# FPGA_Power.net
KiCad netlist of a schematic drawn in Altium Designer
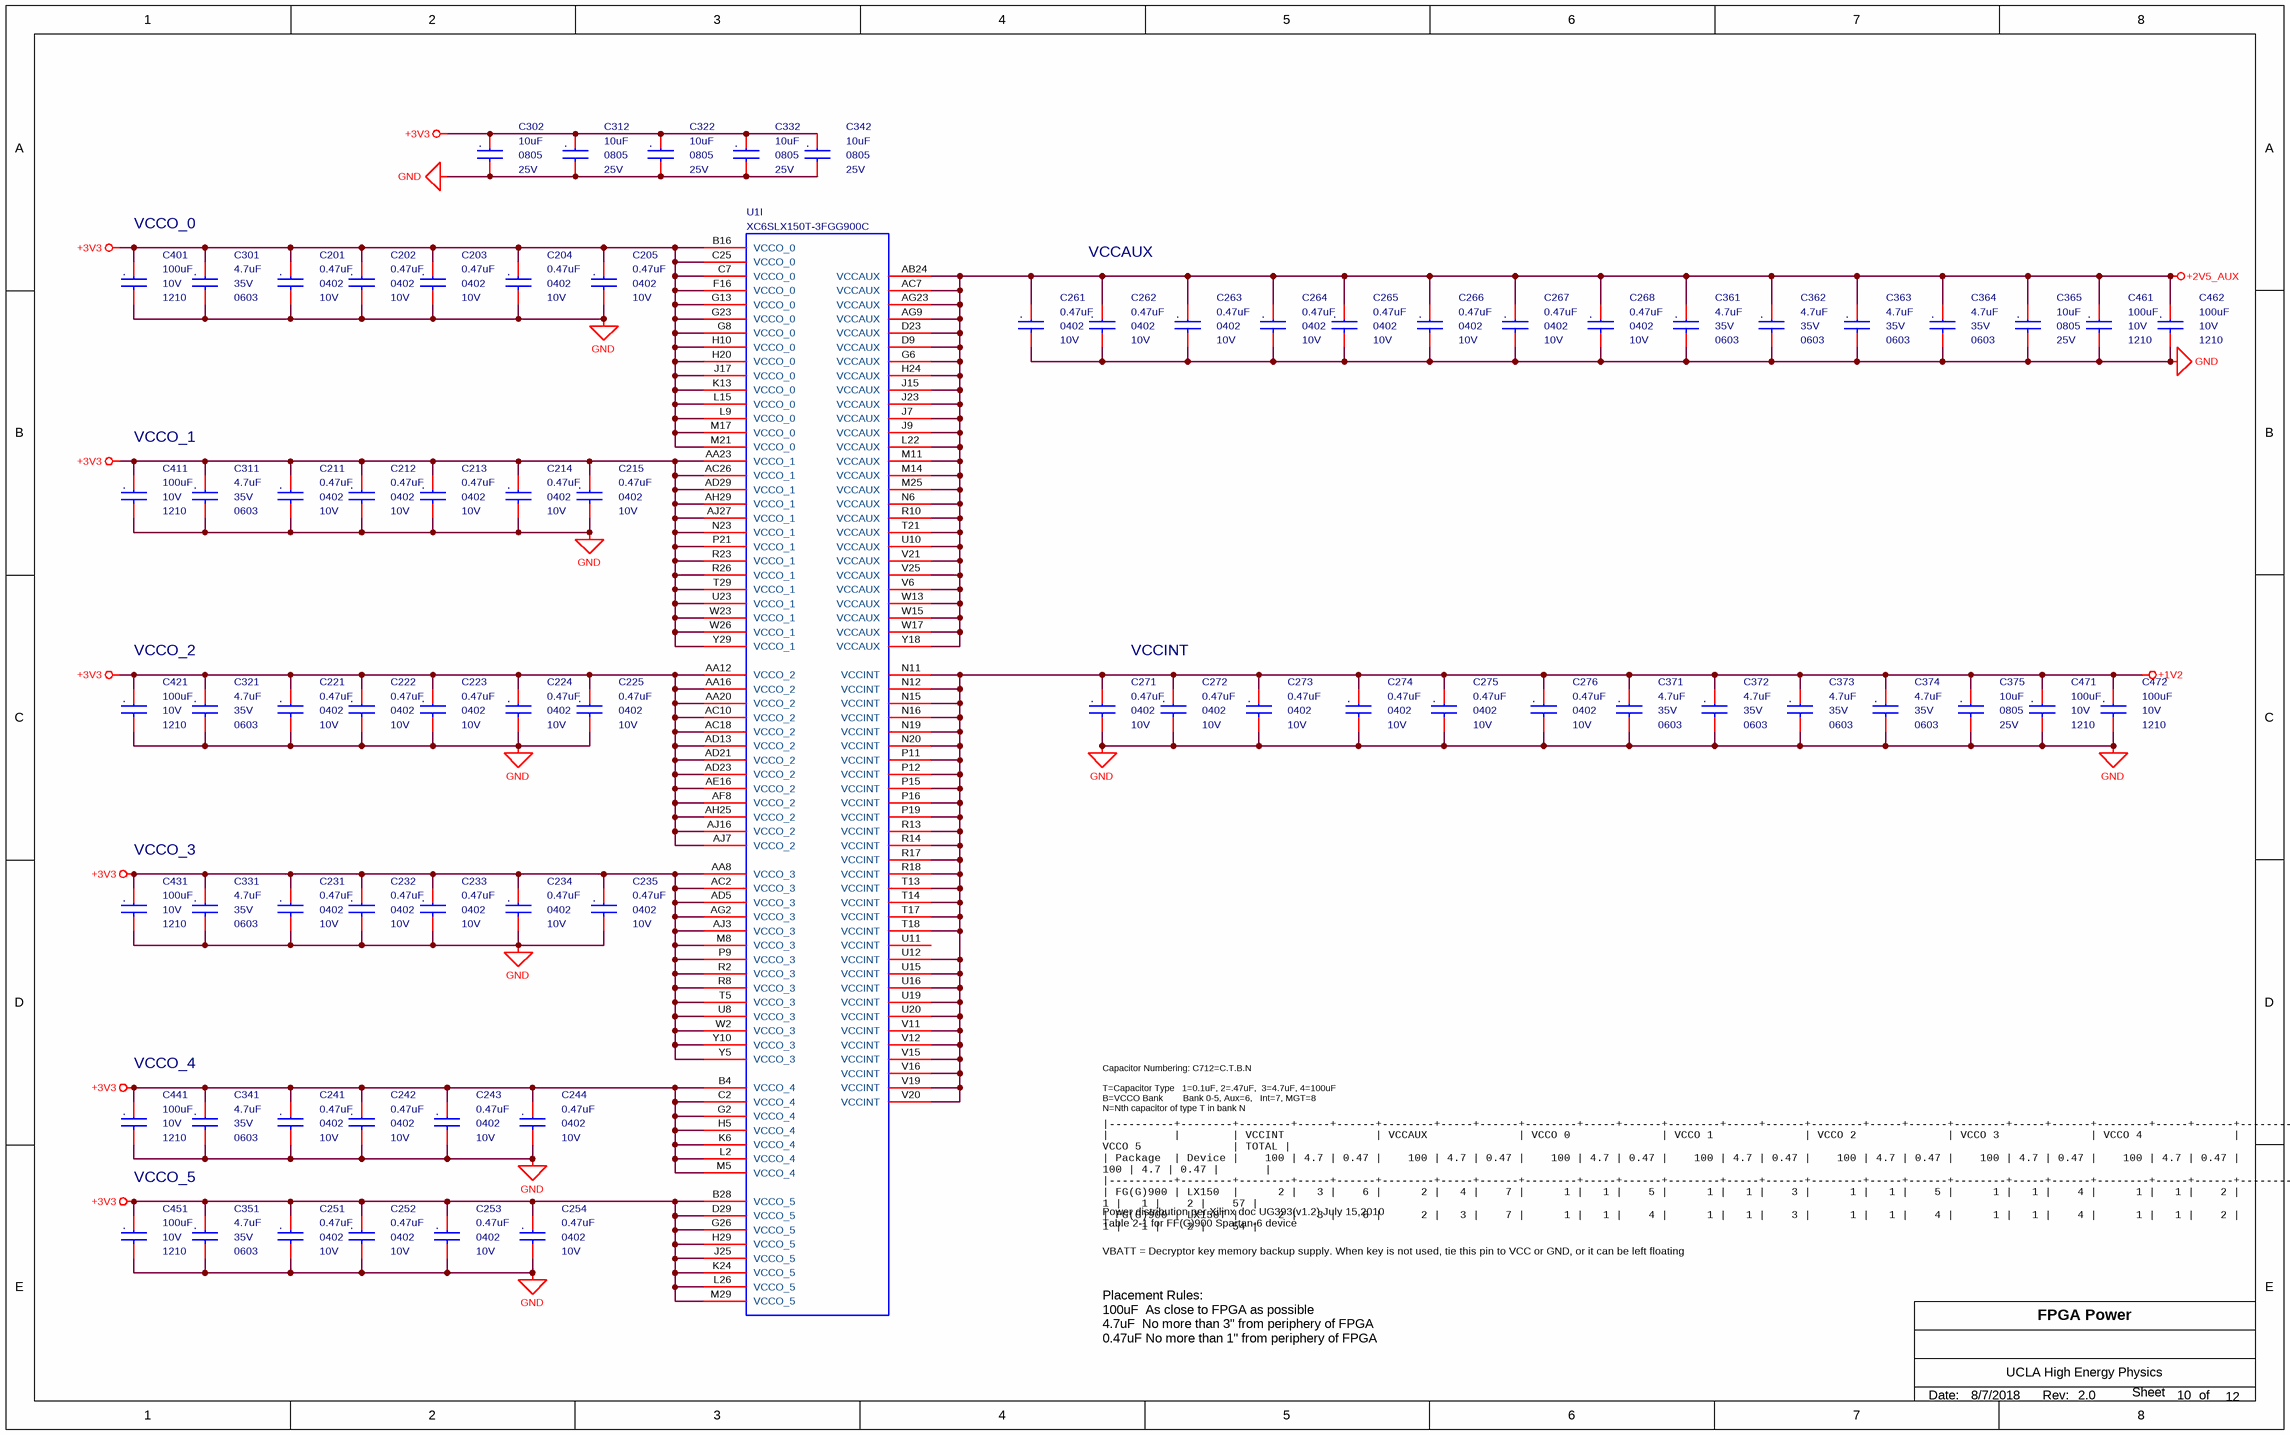
[diagram p0: FPGA_Power.SchDoc]

(export (version "E")
  (design (tool "Eeschema 10.0.6"))
  (components
    (comp (ref "C201")
      (value "0.47uF")
      (footprint "MC_S6/SM/C_0402_IPC")
      (description "CAP CER 0.47UF 10V X5R 0402")
      (fields
        (field (name "MANUFACTURER") "Murata Electronics North America")
        (field (name "MANUFACTURER PART NUMBER") "GRM155R61A474KE15J")
        (field (name "VOLTAGE - RATED") "10V")
        (field (name "PACKAGE") "0402")
      )
      (libsource (lib "ALCT_MEZ_SPARTAN6_Library") (part "GRM155R61A474KE15J"))
    )
    (comp (ref "C202")
      (value "0.47uF")
      (footprint "MC_S6/SM/C_0402_IPC")
      (description "CAP CER 0.47UF 10V X5R 0402")
      (fields
        (field (name "MANUFACTURER") "Murata Electronics North America")
        (field (name "MANUFACTURER PART NUMBER") "GRM155R61A474KE15J")
        (field (name "VOLTAGE - RATED") "10V")
        (field (name "PACKAGE") "0402")
      )
      (libsource (lib "ALCT_MEZ_SPARTAN6_Library") (part "GRM155R61A474KE15J"))
    )
    (comp (ref "C203")
      (value "0.47uF")
      (footprint "MC_S6/SM/C_0402_IPC")
      (description "CAP CER 0.47UF 10V X5R 0402")
      (fields
        (field (name "MANUFACTURER") "Murata Electronics North America")
        (field (name "MANUFACTURER PART NUMBER") "GRM155R61A474KE15J")
        (field (name "VOLTAGE - RATED") "10V")
        (field (name "PACKAGE") "0402")
      )
      (libsource (lib "ALCT_MEZ_SPARTAN6_Library") (part "GRM155R61A474KE15J"))
    )
    (comp (ref "C204")
      (value "0.47uF")
      (footprint "MC_S6/SM/C_0402_IPC")
      (description "CAP CER 0.47UF 10V X5R 0402")
      (fields
        (field (name "MANUFACTURER") "Murata Electronics North America")
        (field (name "MANUFACTURER PART NUMBER") "GRM155R61A474KE15J")
        (field (name "VOLTAGE - RATED") "10V")
        (field (name "PACKAGE") "0402")
      )
      (libsource (lib "ALCT_MEZ_SPARTAN6_Library") (part "GRM155R61A474KE15J"))
    )
    (comp (ref "C205")
      (value "0.47uF")
      (footprint "MC_S6/SM/C_0402_IPC")
      (description "CAP CER 0.47UF 10V X5R 0402")
      (fields
        (field (name "MANUFACTURER") "Murata Electronics North America")
        (field (name "MANUFACTURER PART NUMBER") "GRM155R61A474KE15J")
        (field (name "VOLTAGE - RATED") "10V")
        (field (name "PACKAGE") "0402")
      )
      (libsource (lib "ALCT_MEZ_SPARTAN6_Library") (part "GRM155R61A474KE15J"))
    )
    (comp (ref "C211")
      (value "0.47uF")
      (footprint "MC_S6/SM/C_0402_IPC")
      (description "CAP CER 0.47UF 10V X5R 0402")
      (fields
        (field (name "MANUFACTURER") "Murata Electronics North America")
        (field (name "MANUFACTURER PART NUMBER") "GRM155R61A474KE15J")
        (field (name "VOLTAGE - RATED") "10V")
        (field (name "PACKAGE") "0402")
      )
      (libsource (lib "ALCT_MEZ_SPARTAN6_Library") (part "GRM155R61A474KE15J"))
    )
    (comp (ref "C212")
      (value "0.47uF")
      (footprint "MC_S6/SM/C_0402_IPC")
      (description "CAP CER 0.47UF 10V X5R 0402")
      (fields
        (field (name "MANUFACTURER") "Murata Electronics North America")
        (field (name "MANUFACTURER PART NUMBER") "GRM155R61A474KE15J")
        (field (name "VOLTAGE - RATED") "10V")
        (field (name "PACKAGE") "0402")
      )
      (libsource (lib "ALCT_MEZ_SPARTAN6_Library") (part "GRM155R61A474KE15J"))
    )
    (comp (ref "C213")
      (value "0.47uF")
      (footprint "MC_S6/SM/C_0402_IPC")
      (description "CAP CER 0.47UF 10V X5R 0402")
      (fields
        (field (name "MANUFACTURER") "Murata Electronics North America")
        (field (name "MANUFACTURER PART NUMBER") "GRM155R61A474KE15J")
        (field (name "VOLTAGE - RATED") "10V")
        (field (name "PACKAGE") "0402")
      )
      (libsource (lib "ALCT_MEZ_SPARTAN6_Library") (part "GRM155R61A474KE15J"))
    )
    (comp (ref "C214")
      (value "0.47uF")
      (footprint "MC_S6/SM/C_0402_IPC")
      (description "CAP CER 0.47UF 10V X5R 0402")
      (fields
        (field (name "MANUFACTURER") "Murata Electronics North America")
        (field (name "MANUFACTURER PART NUMBER") "GRM155R61A474KE15J")
        (field (name "VOLTAGE - RATED") "10V")
        (field (name "PACKAGE") "0402")
      )
      (libsource (lib "ALCT_MEZ_SPARTAN6_Library") (part "GRM155R61A474KE15J"))
    )
    (comp (ref "C215")
      (value "0.47uF")
      (footprint "MC_S6/SM/C_0402_IPC")
      (description "CAP CER 0.47UF 10V X5R 0402")
      (fields
        (field (name "MANUFACTURER") "Murata Electronics North America")
        (field (name "MANUFACTURER PART NUMBER") "GRM155R61A474KE15J")
        (field (name "VOLTAGE - RATED") "10V")
        (field (name "PACKAGE") "0402")
      )
      (libsource (lib "ALCT_MEZ_SPARTAN6_Library") (part "GRM155R61A474KE15J"))
    )
    (comp (ref "C221")
      (value "0.47uF")
      (footprint "MC_S6/SM/C_0402_IPC")
      (description "CAP CER 0.47UF 10V X5R 0402")
      (fields
        (field (name "MANUFACTURER") "Murata Electronics North America")
        (field (name "MANUFACTURER PART NUMBER") "GRM155R61A474KE15J")
        (field (name "VOLTAGE - RATED") "10V")
        (field (name "PACKAGE") "0402")
      )
      (libsource (lib "ALCT_MEZ_SPARTAN6_Library") (part "GRM155R61A474KE15J"))
    )
    (comp (ref "C222")
      (value "0.47uF")
      (footprint "MC_S6/SM/C_0402_IPC")
      (description "CAP CER 0.47UF 10V X5R 0402")
      (fields
        (field (name "MANUFACTURER") "Murata Electronics North America")
        (field (name "MANUFACTURER PART NUMBER") "GRM155R61A474KE15J")
        (field (name "VOLTAGE - RATED") "10V")
        (field (name "PACKAGE") "0402")
      )
      (libsource (lib "ALCT_MEZ_SPARTAN6_Library") (part "GRM155R61A474KE15J"))
    )
    (comp (ref "C223")
      (value "0.47uF")
      (footprint "MC_S6/SM/C_0402_IPC")
      (description "CAP CER 0.47UF 10V X5R 0402")
      (fields
        (field (name "MANUFACTURER") "Murata Electronics North America")
        (field (name "MANUFACTURER PART NUMBER") "GRM155R61A474KE15J")
        (field (name "VOLTAGE - RATED") "10V")
        (field (name "PACKAGE") "0402")
      )
      (libsource (lib "ALCT_MEZ_SPARTAN6_Library") (part "GRM155R61A474KE15J"))
    )
    (comp (ref "C224")
      (value "0.47uF")
      (footprint "MC_S6/SM/C_0402_IPC")
      (description "CAP CER 0.47UF 10V X5R 0402")
      (fields
        (field (name "MANUFACTURER") "Murata Electronics North America")
        (field (name "MANUFACTURER PART NUMBER") "GRM155R61A474KE15J")
        (field (name "VOLTAGE - RATED") "10V")
        (field (name "PACKAGE") "0402")
      )
      (libsource (lib "ALCT_MEZ_SPARTAN6_Library") (part "GRM155R61A474KE15J"))
    )
    (comp (ref "C225")
      (value "0.47uF")
      (footprint "MC_S6/SM/C_0402_IPC")
      (description "CAP CER 0.47UF 10V X5R 0402")
      (fields
        (field (name "MANUFACTURER") "Murata Electronics North America")
        (field (name "MANUFACTURER PART NUMBER") "GRM155R61A474KE15J")
        (field (name "VOLTAGE - RATED") "10V")
        (field (name "PACKAGE") "0402")
      )
      (libsource (lib "ALCT_MEZ_SPARTAN6_Library") (part "GRM155R61A474KE15J"))
    )
    (comp (ref "C231")
      (value "0.47uF")
      (footprint "MC_S6/SM/C_0402_IPC")
      (description "CAP CER 0.47UF 10V X5R 0402")
      (fields
        (field (name "MANUFACTURER") "Murata Electronics North America")
        (field (name "MANUFACTURER PART NUMBER") "GRM155R61A474KE15J")
        (field (name "VOLTAGE - RATED") "10V")
        (field (name "PACKAGE") "0402")
      )
      (libsource (lib "ALCT_MEZ_SPARTAN6_Library") (part "GRM155R61A474KE15J"))
    )
    (comp (ref "C232")
      (value "0.47uF")
      (footprint "MC_S6/SM/C_0402_IPC")
      (description "CAP CER 0.47UF 10V X5R 0402")
      (fields
        (field (name "MANUFACTURER") "Murata Electronics North America")
        (field (name "MANUFACTURER PART NUMBER") "GRM155R61A474KE15J")
        (field (name "VOLTAGE - RATED") "10V")
        (field (name "PACKAGE") "0402")
      )
      (libsource (lib "ALCT_MEZ_SPARTAN6_Library") (part "GRM155R61A474KE15J"))
    )
    (comp (ref "C233")
      (value "0.47uF")
      (footprint "MC_S6/SM/C_0402_IPC")
      (description "CAP CER 0.47UF 10V X5R 0402")
      (fields
        (field (name "MANUFACTURER") "Murata Electronics North America")
        (field (name "MANUFACTURER PART NUMBER") "GRM155R61A474KE15J")
        (field (name "VOLTAGE - RATED") "10V")
        (field (name "PACKAGE") "0402")
      )
      (libsource (lib "ALCT_MEZ_SPARTAN6_Library") (part "GRM155R61A474KE15J"))
    )
    (comp (ref "C234")
      (value "0.47uF")
      (footprint "MC_S6/SM/C_0402_IPC")
      (description "CAP CER 0.47UF 10V X5R 0402")
      (fields
        (field (name "MANUFACTURER") "Murata Electronics North America")
        (field (name "MANUFACTURER PART NUMBER") "GRM155R61A474KE15J")
        (field (name "VOLTAGE - RATED") "10V")
        (field (name "PACKAGE") "0402")
      )
      (libsource (lib "ALCT_MEZ_SPARTAN6_Library") (part "GRM155R61A474KE15J"))
    )
    (comp (ref "C235")
      (value "0.47uF")
      (footprint "MC_S6/SM/C_0402_IPC")
      (description "CAP CER 0.47UF 10V X5R 0402")
      (fields
        (field (name "MANUFACTURER") "Murata Electronics North America")
        (field (name "MANUFACTURER PART NUMBER") "GRM155R61A474KE15J")
        (field (name "VOLTAGE - RATED") "10V")
        (field (name "PACKAGE") "0402")
      )
      (libsource (lib "ALCT_MEZ_SPARTAN6_Library") (part "GRM155R61A474KE15J"))
    )
    (comp (ref "C241")
      (value "0.47uF")
      (footprint "MC_S6/SM/C_0402_IPC")
      (description "CAP CER 0.47UF 10V X5R 0402")
      (fields
        (field (name "MANUFACTURER") "Murata Electronics North America")
        (field (name "MANUFACTURER PART NUMBER") "GRM155R61A474KE15J")
        (field (name "VOLTAGE - RATED") "10V")
        (field (name "PACKAGE") "0402")
      )
      (libsource (lib "ALCT_MEZ_SPARTAN6_Library") (part "GRM155R61A474KE15J"))
    )
    (comp (ref "C242")
      (value "0.47uF")
      (footprint "MC_S6/SM/C_0402_IPC")
      (description "CAP CER 0.47UF 10V X5R 0402")
      (fields
        (field (name "MANUFACTURER") "Murata Electronics North America")
        (field (name "MANUFACTURER PART NUMBER") "GRM155R61A474KE15J")
        (field (name "VOLTAGE - RATED") "10V")
        (field (name "PACKAGE") "0402")
      )
      (libsource (lib "ALCT_MEZ_SPARTAN6_Library") (part "GRM155R61A474KE15J"))
    )
    (comp (ref "C243")
      (value "0.47uF")
      (footprint "MC_S6/SM/C_0402_IPC")
      (description "CAP CER 0.47UF 10V X5R 0402")
      (fields
        (field (name "MANUFACTURER") "Murata Electronics North America")
        (field (name "MANUFACTURER PART NUMBER") "GRM155R61A474KE15J")
        (field (name "VOLTAGE - RATED") "10V")
        (field (name "PACKAGE") "0402")
      )
      (libsource (lib "ALCT_MEZ_SPARTAN6_Library") (part "GRM155R61A474KE15J"))
    )
    (comp (ref "C244")
      (value "0.47uF")
      (footprint "MC_S6/SM/C_0402_IPC")
      (description "CAP CER 0.47UF 10V X5R 0402")
      (fields
        (field (name "MANUFACTURER") "Murata Electronics North America")
        (field (name "MANUFACTURER PART NUMBER") "GRM155R61A474KE15J")
        (field (name "VOLTAGE - RATED") "10V")
        (field (name "PACKAGE") "0402")
      )
      (libsource (lib "ALCT_MEZ_SPARTAN6_Library") (part "GRM155R61A474KE15J"))
    )
    (comp (ref "C251")
      (value "0.47uF")
      (footprint "MC_S6/SM/C_0402_IPC")
      (description "CAP CER 0.47UF 10V X5R 0402")
      (fields
        (field (name "MANUFACTURER") "Murata Electronics North America")
        (field (name "MANUFACTURER PART NUMBER") "GRM155R61A474KE15J")
        (field (name "VOLTAGE - RATED") "10V")
        (field (name "PACKAGE") "0402")
      )
      (libsource (lib "ALCT_MEZ_SPARTAN6_Library") (part "GRM155R61A474KE15J"))
    )
    (comp (ref "C252")
      (value "0.47uF")
      (footprint "MC_S6/SM/C_0402_IPC")
      (description "CAP CER 0.47UF 10V X5R 0402")
      (fields
        (field (name "MANUFACTURER") "Murata Electronics North America")
        (field (name "MANUFACTURER PART NUMBER") "GRM155R61A474KE15J")
        (field (name "VOLTAGE - RATED") "10V")
        (field (name "PACKAGE") "0402")
      )
      (libsource (lib "ALCT_MEZ_SPARTAN6_Library") (part "GRM155R61A474KE15J"))
    )
    (comp (ref "C253")
      (value "0.47uF")
      (footprint "MC_S6/SM/C_0402_IPC")
      (description "CAP CER 0.47UF 10V X5R 0402")
      (fields
        (field (name "MANUFACTURER") "Murata Electronics North America")
        (field (name "MANUFACTURER PART NUMBER") "GRM155R61A474KE15J")
        (field (name "VOLTAGE - RATED") "10V")
        (field (name "PACKAGE") "0402")
      )
      (libsource (lib "ALCT_MEZ_SPARTAN6_Library") (part "GRM155R61A474KE15J"))
    )
    (comp (ref "C254")
      (value "0.47uF")
      (footprint "MC_S6/SM/C_0402_IPC")
      (description "CAP CER 0.47UF 10V X5R 0402")
      (fields
        (field (name "MANUFACTURER") "Murata Electronics North America")
        (field (name "MANUFACTURER PART NUMBER") "GRM155R61A474KE15J")
        (field (name "VOLTAGE - RATED") "10V")
        (field (name "PACKAGE") "0402")
      )
      (libsource (lib "ALCT_MEZ_SPARTAN6_Library") (part "GRM155R61A474KE15J"))
    )
    (comp (ref "C261")
      (value "0.47uF")
      (footprint "MC_S6/SM/C_0402_IPC")
      (description "CAP CER 0.47UF 10V X5R 0402")
      (fields
        (field (name "MANUFACTURER") "Murata Electronics North America")
        (field (name "MANUFACTURER PART NUMBER") "GRM155R61A474KE15J")
        (field (name "VOLTAGE - RATED") "10V")
        (field (name "PACKAGE") "0402")
      )
      (libsource (lib "ALCT_MEZ_SPARTAN6_Library") (part "GRM155R61A474KE15J"))
    )
    (comp (ref "C262")
      (value "0.47uF")
      (footprint "MC_S6/SM/C_0402_IPC")
      (description "CAP CER 0.47UF 10V X5R 0402")
      (fields
        (field (name "MANUFACTURER") "Murata Electronics North America")
        (field (name "MANUFACTURER PART NUMBER") "GRM155R61A474KE15J")
        (field (name "VOLTAGE - RATED") "10V")
        (field (name "PACKAGE") "0402")
      )
      (libsource (lib "ALCT_MEZ_SPARTAN6_Library") (part "GRM155R61A474KE15J"))
    )
    (comp (ref "C263")
      (value "0.47uF")
      (footprint "MC_S6/SM/C_0402_IPC")
      (description "CAP CER 0.47UF 10V X5R 0402")
      (fields
        (field (name "MANUFACTURER") "Murata Electronics North America")
        (field (name "MANUFACTURER PART NUMBER") "GRM155R61A474KE15J")
        (field (name "VOLTAGE - RATED") "10V")
        (field (name "PACKAGE") "0402")
      )
      (libsource (lib "ALCT_MEZ_SPARTAN6_Library") (part "GRM155R61A474KE15J"))
    )
    (comp (ref "C264")
      (value "0.47uF")
      (footprint "MC_S6/SM/C_0402_IPC")
      (description "CAP CER 0.47UF 10V X5R 0402")
      (fields
        (field (name "MANUFACTURER") "Murata Electronics North America")
        (field (name "MANUFACTURER PART NUMBER") "GRM155R61A474KE15J")
        (field (name "VOLTAGE - RATED") "10V")
        (field (name "PACKAGE") "0402")
      )
      (libsource (lib "ALCT_MEZ_SPARTAN6_Library") (part "GRM155R61A474KE15J"))
    )
    (comp (ref "C265")
      (value "0.47uF")
      (footprint "MC_S6/SM/C_0402_IPC")
      (description "CAP CER 0.47UF 10V X5R 0402")
      (fields
        (field (name "MANUFACTURER") "Murata Electronics North America")
        (field (name "MANUFACTURER PART NUMBER") "GRM155R61A474KE15J")
        (field (name "VOLTAGE - RATED") "10V")
        (field (name "PACKAGE") "0402")
      )
      (libsource (lib "ALCT_MEZ_SPARTAN6_Library") (part "GRM155R61A474KE15J"))
    )
    (comp (ref "C266")
      (value "0.47uF")
      (footprint "MC_S6/SM/C_0402_IPC")
      (description "CAP CER 0.47UF 10V X5R 0402")
      (fields
        (field (name "MANUFACTURER") "Murata Electronics North America")
        (field (name "MANUFACTURER PART NUMBER") "GRM155R61A474KE15J")
        (field (name "VOLTAGE - RATED") "10V")
        (field (name "PACKAGE") "0402")
      )
      (libsource (lib "ALCT_MEZ_SPARTAN6_Library") (part "GRM155R61A474KE15J"))
    )
    (comp (ref "C267")
      (value "0.47uF")
      (footprint "MC_S6/SM/C_0402_IPC")
      (description "CAP CER 0.47UF 10V X5R 0402")
      (fields
        (field (name "MANUFACTURER") "Murata Electronics North America")
        (field (name "MANUFACTURER PART NUMBER") "GRM155R61A474KE15J")
        (field (name "VOLTAGE - RATED") "10V")
        (field (name "PACKAGE") "0402")
      )
      (libsource (lib "ALCT_MEZ_SPARTAN6_Library") (part "GRM155R61A474KE15J"))
    )
    (comp (ref "C268")
      (value "0.47uF")
      (footprint "MC_S6/SM/C_0402_IPC")
      (description "CAP CER 0.47UF 10V X5R 0402")
      (fields
        (field (name "MANUFACTURER") "Murata Electronics North America")
        (field (name "MANUFACTURER PART NUMBER") "GRM155R61A474KE15J")
        (field (name "VOLTAGE - RATED") "10V")
        (field (name "PACKAGE") "0402")
      )
      (libsource (lib "ALCT_MEZ_SPARTAN6_Library") (part "GRM155R61A474KE15J"))
    )
    (comp (ref "C271")
      (value "0.47uF")
      (footprint "MC_S6/SM/C_0402_IPC")
      (description "CAP CER 0.47UF 10V X5R 0402")
      (fields
        (field (name "MANUFACTURER") "Murata Electronics North America")
        (field (name "MANUFACTURER PART NUMBER") "GRM155R61A474KE15J")
        (field (name "VOLTAGE - RATED") "10V")
        (field (name "PACKAGE") "0402")
      )
      (libsource (lib "ALCT_MEZ_SPARTAN6_Library") (part "GRM155R61A474KE15J"))
    )
    (comp (ref "C272")
      (value "0.47uF")
      (footprint "MC_S6/SM/C_0402_IPC")
      (description "CAP CER 0.47UF 10V X5R 0402")
      (fields
        (field (name "MANUFACTURER") "Murata Electronics North America")
        (field (name "MANUFACTURER PART NUMBER") "GRM155R61A474KE15J")
        (field (name "VOLTAGE - RATED") "10V")
        (field (name "PACKAGE") "0402")
      )
      (libsource (lib "ALCT_MEZ_SPARTAN6_Library") (part "GRM155R61A474KE15J"))
    )
    (comp (ref "C273")
      (value "0.47uF")
      (footprint "MC_S6/SM/C_0402_IPC")
      (description "CAP CER 0.47UF 10V X5R 0402")
      (fields
        (field (name "MANUFACTURER") "Murata Electronics North America")
        (field (name "MANUFACTURER PART NUMBER") "GRM155R61A474KE15J")
        (field (name "VOLTAGE - RATED") "10V")
        (field (name "PACKAGE") "0402")
      )
      (libsource (lib "ALCT_MEZ_SPARTAN6_Library") (part "GRM155R61A474KE15J"))
    )
    (comp (ref "C274")
      (value "0.47uF")
      (footprint "MC_S6/SM/C_0402_IPC")
      (description "CAP CER 0.47UF 10V X5R 0402")
      (fields
        (field (name "MANUFACTURER") "Murata Electronics North America")
        (field (name "MANUFACTURER PART NUMBER") "GRM155R61A474KE15J")
        (field (name "VOLTAGE - RATED") "10V")
        (field (name "PACKAGE") "0402")
      )
      (libsource (lib "ALCT_MEZ_SPARTAN6_Library") (part "GRM155R61A474KE15J"))
    )
    (comp (ref "C275")
      (value "0.47uF")
      (footprint "MC_S6/SM/C_0402_IPC")
      (description "CAP CER 0.47UF 10V X5R 0402")
      (fields
        (field (name "MANUFACTURER") "Murata Electronics North America")
        (field (name "MANUFACTURER PART NUMBER") "GRM155R61A474KE15J")
        (field (name "VOLTAGE - RATED") "10V")
        (field (name "PACKAGE") "0402")
      )
      (libsource (lib "ALCT_MEZ_SPARTAN6_Library") (part "GRM155R61A474KE15J"))
    )
    (comp (ref "C276")
      (value "0.47uF")
      (footprint "MC_S6/SM/C_0402_IPC")
      (description "CAP CER 0.47UF 10V X5R 0402")
      (fields
        (field (name "MANUFACTURER") "Murata Electronics North America")
        (field (name "MANUFACTURER PART NUMBER") "GRM155R61A474KE15J")
        (field (name "VOLTAGE - RATED") "10V")
        (field (name "PACKAGE") "0402")
      )
      (libsource (lib "ALCT_MEZ_SPARTAN6_Library") (part "GRM155R61A474KE15J"))
    )
    (comp (ref "C301")
      (value "4.7uF")
      (footprint "MC_S6/SM/C_0603_IPC")
      (description "CAP CER 4.7UF 35V X5R 0603")
      (fields
        (field (name "MANUFACTURER") "Murata")
        (field (name "MANUFACTURER PART NUMBER") "GRM188R6YA475KE15D")
        (field (name "VOLTAGE - RATED") "35V")
        (field (name "PACKAGE") "0603")
      )
      (libsource (lib "ALCT_MEZ_SPARTAN6_Library") (part "GRM188R6YA475KE15D"))
    )
    (comp (ref "C302")
      (value "10uF")
      (footprint "MC_S6/SM/C_0805_IPC")
      (description "CAP CER 10UF 25V X5R 0805")
      (fields
        (field (name "MANUFACTURER") "Murata Electronics North America")
        (field (name "MANUFACTURER PART NUMBER") "GRM21BR61E106KA73L")
        (field (name "VOLTAGE - RATED") "25V")
        (field (name "PACKAGE") "0805")
      )
      (libsource (lib "ALCT_MEZ_SPARTAN6_Library") (part "GRM21BR61E106KA73L"))
    )
    (comp (ref "C311")
      (value "4.7uF")
      (footprint "MC_S6/SM/C_0603_IPC")
      (description "CAP CER 4.7UF 35V X5R 0603")
      (fields
        (field (name "MANUFACTURER") "Murata")
        (field (name "MANUFACTURER PART NUMBER") "GRM188R6YA475KE15D")
        (field (name "VOLTAGE - RATED") "35V")
        (field (name "PACKAGE") "0603")
      )
      (libsource (lib "ALCT_MEZ_SPARTAN6_Library") (part "GRM188R6YA475KE15D"))
    )
    (comp (ref "C312")
      (value "10uF")
      (footprint "MC_S6/SM/C_0805_IPC")
      (description "CAP CER 10UF 25V X5R 0805")
      (fields
        (field (name "MANUFACTURER") "Murata Electronics North America")
        (field (name "MANUFACTURER PART NUMBER") "GRM21BR61E106KA73L")
        (field (name "VOLTAGE - RATED") "25V")
        (field (name "PACKAGE") "0805")
      )
      (libsource (lib "ALCT_MEZ_SPARTAN6_Library") (part "GRM21BR61E106KA73L"))
    )
    (comp (ref "C321")
      (value "4.7uF")
      (footprint "MC_S6/SM/C_0603_IPC")
      (description "CAP CER 4.7UF 35V X5R 0603")
      (fields
        (field (name "MANUFACTURER") "Murata")
        (field (name "MANUFACTURER PART NUMBER") "GRM188R6YA475KE15D")
        (field (name "VOLTAGE - RATED") "35V")
        (field (name "PACKAGE") "0603")
      )
      (libsource (lib "ALCT_MEZ_SPARTAN6_Library") (part "GRM188R6YA475KE15D"))
    )
    (comp (ref "C322")
      (value "10uF")
      (footprint "MC_S6/SM/C_0805_IPC")
      (description "CAP CER 10UF 25V X5R 0805")
      (fields
        (field (name "MANUFACTURER") "Murata Electronics North America")
        (field (name "MANUFACTURER PART NUMBER") "GRM21BR61E106KA73L")
        (field (name "VOLTAGE - RATED") "25V")
        (field (name "PACKAGE") "0805")
      )
      (libsource (lib "ALCT_MEZ_SPARTAN6_Library") (part "GRM21BR61E106KA73L"))
    )
    (comp (ref "C331")
      (value "4.7uF")
      (footprint "MC_S6/SM/C_0603_IPC")
      (description "CAP CER 4.7UF 35V X5R 0603")
      (fields
        (field (name "MANUFACTURER") "Murata")
        (field (name "MANUFACTURER PART NUMBER") "GRM188R6YA475KE15D")
        (field (name "VOLTAGE - RATED") "35V")
        (field (name "PACKAGE") "0603")
      )
      (libsource (lib "ALCT_MEZ_SPARTAN6_Library") (part "GRM188R6YA475KE15D"))
    )
    (comp (ref "C332")
      (value "10uF")
      (footprint "MC_S6/SM/C_0805_IPC")
      (description "CAP CER 10UF 25V X5R 0805")
      (fields
        (field (name "MANUFACTURER") "Murata Electronics North America")
        (field (name "MANUFACTURER PART NUMBER") "GRM21BR61E106KA73L")
        (field (name "VOLTAGE - RATED") "25V")
        (field (name "PACKAGE") "0805")
      )
      (libsource (lib "ALCT_MEZ_SPARTAN6_Library") (part "GRM21BR61E106KA73L"))
    )
    (comp (ref "C341")
      (value "4.7uF")
      (footprint "MC_S6/SM/C_0603_IPC")
      (description "CAP CER 4.7UF 35V X5R 0603")
      (fields
        (field (name "MANUFACTURER") "Murata")
        (field (name "MANUFACTURER PART NUMBER") "GRM188R6YA475KE15D")
        (field (name "VOLTAGE - RATED") "35V")
        (field (name "PACKAGE") "0603")
      )
      (libsource (lib "ALCT_MEZ_SPARTAN6_Library") (part "GRM188R6YA475KE15D"))
    )
    (comp (ref "C342")
      (value "10uF")
      (footprint "MC_S6/SM/C_0805_IPC")
      (description "CAP CER 10UF 25V X5R 0805")
      (fields
        (field (name "MANUFACTURER") "Murata Electronics North America")
        (field (name "MANUFACTURER PART NUMBER") "GRM21BR61E106KA73L")
        (field (name "VOLTAGE - RATED") "25V")
        (field (name "PACKAGE") "0805")
      )
      (libsource (lib "ALCT_MEZ_SPARTAN6_Library") (part "GRM21BR61E106KA73L"))
    )
    (comp (ref "C351")
      (value "4.7uF")
      (footprint "MC_S6/SM/C_0603_IPC")
      (description "CAP CER 4.7UF 35V X5R 0603")
      (fields
        (field (name "MANUFACTURER") "Murata")
        (field (name "MANUFACTURER PART NUMBER") "GRM188R6YA475KE15D")
        (field (name "VOLTAGE - RATED") "35V")
        (field (name "PACKAGE") "0603")
      )
      (libsource (lib "ALCT_MEZ_SPARTAN6_Library") (part "GRM188R6YA475KE15D"))
    )
    (comp (ref "C361")
      (value "4.7uF")
      (footprint "MC_S6/SM/C_0603_IPC")
      (description "CAP CER 4.7UF 35V X5R 0603")
      (fields
        (field (name "MANUFACTURER") "Murata")
        (field (name "MANUFACTURER PART NUMBER") "GRM188R6YA475KE15D")
        (field (name "VOLTAGE - RATED") "35V")
        (field (name "PACKAGE") "0603")
      )
      (libsource (lib "ALCT_MEZ_SPARTAN6_Library") (part "GRM188R6YA475KE15D"))
    )
    (comp (ref "C362")
      (value "4.7uF")
      (footprint "MC_S6/SM/C_0603_IPC")
      (description "CAP CER 4.7UF 35V X5R 0603")
      (fields
        (field (name "MANUFACTURER") "Murata")
        (field (name "MANUFACTURER PART NUMBER") "GRM188R6YA475KE15D")
        (field (name "VOLTAGE - RATED") "35V")
        (field (name "PACKAGE") "0603")
      )
      (libsource (lib "ALCT_MEZ_SPARTAN6_Library") (part "GRM188R6YA475KE15D"))
    )
    (comp (ref "C363")
      (value "4.7uF")
      (footprint "MC_S6/SM/C_0603_IPC")
      (description "CAP CER 4.7UF 35V X5R 0603")
      (fields
        (field (name "MANUFACTURER") "Murata")
        (field (name "MANUFACTURER PART NUMBER") "GRM188R6YA475KE15D")
        (field (name "VOLTAGE - RATED") "35V")
        (field (name "PACKAGE") "0603")
      )
      (libsource (lib "ALCT_MEZ_SPARTAN6_Library") (part "GRM188R6YA475KE15D"))
    )
    (comp (ref "C364")
      (value "4.7uF")
      (footprint "MC_S6/SM/C_0603_IPC")
      (description "CAP CER 4.7UF 35V X5R 0603")
      (fields
        (field (name "MANUFACTURER") "Murata")
        (field (name "MANUFACTURER PART NUMBER") "GRM188R6YA475KE15D")
        (field (name "VOLTAGE - RATED") "35V")
        (field (name "PACKAGE") "0603")
      )
      (libsource (lib "ALCT_MEZ_SPARTAN6_Library") (part "GRM188R6YA475KE15D"))
    )
    (comp (ref "C365")
      (value "10uF")
      (footprint "MC_S6/SM/C_0805_IPC")
      (description "CAP CER 10UF 25V X5R 0805")
      (fields
        (field (name "MANUFACTURER") "Murata Electronics North America")
        (field (name "MANUFACTURER PART NUMBER") "GRM21BR61E106KA73L")
        (field (name "VOLTAGE - RATED") "25V")
        (field (name "PACKAGE") "0805")
      )
      (libsource (lib "ALCT_MEZ_SPARTAN6_Library") (part "GRM21BR61E106KA73L"))
    )
    (comp (ref "C371")
      (value "4.7uF")
      (footprint "MC_S6/SM/C_0603_IPC")
      (description "CAP CER 4.7UF 35V X5R 0603")
      (fields
        (field (name "MANUFACTURER") "Murata")
        (field (name "MANUFACTURER PART NUMBER") "GRM188R6YA475KE15D")
        (field (name "VOLTAGE - RATED") "35V")
        (field (name "PACKAGE") "0603")
      )
      (libsource (lib "ALCT_MEZ_SPARTAN6_Library") (part "GRM188R6YA475KE15D"))
    )
    (comp (ref "C372")
      (value "4.7uF")
      (footprint "MC_S6/SM/C_0603_IPC")
      (description "CAP CER 4.7UF 35V X5R 0603")
      (fields
        (field (name "MANUFACTURER") "Murata")
        (field (name "MANUFACTURER PART NUMBER") "GRM188R6YA475KE15D")
        (field (name "VOLTAGE - RATED") "35V")
        (field (name "PACKAGE") "0603")
      )
      (libsource (lib "ALCT_MEZ_SPARTAN6_Library") (part "GRM188R6YA475KE15D"))
    )
    (comp (ref "C373")
      (value "4.7uF")
      (footprint "MC_S6/SM/C_0603_IPC")
      (description "CAP CER 4.7UF 35V X5R 0603")
      (fields
        (field (name "MANUFACTURER") "Murata")
        (field (name "MANUFACTURER PART NUMBER") "GRM188R6YA475KE15D")
        (field (name "VOLTAGE - RATED") "35V")
        (field (name "PACKAGE") "0603")
      )
      (libsource (lib "ALCT_MEZ_SPARTAN6_Library") (part "GRM188R6YA475KE15D"))
    )
    (comp (ref "C374")
      (value "4.7uF")
      (footprint "MC_S6/SM/C_0603_IPC")
      (description "CAP CER 4.7UF 35V X5R 0603")
      (fields
        (field (name "MANUFACTURER") "Murata")
        (field (name "MANUFACTURER PART NUMBER") "GRM188R6YA475KE15D")
        (field (name "VOLTAGE - RATED") "35V")
        (field (name "PACKAGE") "0603")
      )
      (libsource (lib "ALCT_MEZ_SPARTAN6_Library") (part "GRM188R6YA475KE15D"))
    )
    (comp (ref "C375")
      (value "10uF")
      (footprint "MC_S6/SM/C_0805_IPC")
      (description "CAP CER 10UF 25V X5R 0805")
      (fields
        (field (name "MANUFACTURER") "Murata Electronics North America")
        (field (name "MANUFACTURER PART NUMBER") "GRM21BR61E106KA73L")
        (field (name "VOLTAGE - RATED") "25V")
        (field (name "PACKAGE") "0805")
      )
      (libsource (lib "ALCT_MEZ_SPARTAN6_Library") (part "GRM21BR61E106KA73L"))
    )
    (comp (ref "C401")
      (value "100uF")
      (footprint "MC_S6/SM/C_1210_IPC")
      (description "CAP CER 100UF 10V X5R 1210")
      (fields
        (field (name "MANUFACTURER") "Taiyo Yuden")
        (field (name "MANUFACTURER PART NUMBER") "LMK325BJ107MM-T")
        (field (name "VOLTAGE - RATED") "10V")
        (field (name "PACKAGE") "1210")
      )
      (libsource (lib "ALCT_MEZ_SPARTAN6_Library") (part "LMK325BJ107MM-T"))
    )
    (comp (ref "C411")
      (value "100uF")
      (footprint "MC_S6/SM/C_1210_IPC")
      (description "CAP CER 100UF 10V X5R 1210")
      (fields
        (field (name "MANUFACTURER") "Taiyo Yuden")
        (field (name "MANUFACTURER PART NUMBER") "LMK325BJ107MM-T")
        (field (name "VOLTAGE - RATED") "10V")
        (field (name "PACKAGE") "1210")
      )
      (libsource (lib "ALCT_MEZ_SPARTAN6_Library") (part "LMK325BJ107MM-T"))
    )
    (comp (ref "C421")
      (value "100uF")
      (footprint "MC_S6/SM/C_1210_IPC")
      (description "CAP CER 100UF 10V X5R 1210")
      (fields
        (field (name "MANUFACTURER") "Taiyo Yuden")
        (field (name "MANUFACTURER PART NUMBER") "LMK325BJ107MM-T")
        (field (name "VOLTAGE - RATED") "10V")
        (field (name "PACKAGE") "1210")
      )
      (libsource (lib "ALCT_MEZ_SPARTAN6_Library") (part "LMK325BJ107MM-T"))
    )
    (comp (ref "C431")
      (value "100uF")
      (footprint "MC_S6/SM/C_1210_IPC")
      (description "CAP CER 100UF 10V X5R 1210")
      (fields
        (field (name "MANUFACTURER") "Taiyo Yuden")
        (field (name "MANUFACTURER PART NUMBER") "LMK325BJ107MM-T")
        (field (name "VOLTAGE - RATED") "10V")
        (field (name "PACKAGE") "1210")
      )
      (libsource (lib "ALCT_MEZ_SPARTAN6_Library") (part "LMK325BJ107MM-T"))
    )
    (comp (ref "C441")
      (value "100uF")
      (footprint "MC_S6/SM/C_1210_IPC")
      (description "CAP CER 100UF 10V X5R 1210")
      (fields
        (field (name "MANUFACTURER") "Taiyo Yuden")
        (field (name "MANUFACTURER PART NUMBER") "LMK325BJ107MM-T")
        (field (name "VOLTAGE - RATED") "10V")
        (field (name "PACKAGE") "1210")
      )
      (libsource (lib "ALCT_MEZ_SPARTAN6_Library") (part "LMK325BJ107MM-T"))
    )
    (comp (ref "C451")
      (value "100uF")
      (footprint "MC_S6/SM/C_1210_IPC")
      (description "CAP CER 100UF 10V X5R 1210")
      (fields
        (field (name "MANUFACTURER") "Taiyo Yuden")
        (field (name "MANUFACTURER PART NUMBER") "LMK325BJ107MM-T")
        (field (name "VOLTAGE - RATED") "10V")
        (field (name "PACKAGE") "1210")
      )
      (libsource (lib "ALCT_MEZ_SPARTAN6_Library") (part "LMK325BJ107MM-T"))
    )
    (comp (ref "C461")
      (value "100uF")
      (footprint "MC_S6/SM/C_1210_IPC")
      (description "CAP CER 100UF 10V X5R 1210")
      (fields
        (field (name "MANUFACTURER") "Taiyo Yuden")
        (field (name "MANUFACTURER PART NUMBER") "LMK325BJ107MM-T")
        (field (name "VOLTAGE - RATED") "10V")
        (field (name "PACKAGE") "1210")
      )
      (libsource (lib "ALCT_MEZ_SPARTAN6_Library") (part "LMK325BJ107MM-T"))
    )
    (comp (ref "C462")
      (value "100uF")
      (footprint "MC_S6/SM/C_1210_IPC")
      (description "CAP CER 100UF 10V X5R 1210")
      (fields
        (field (name "MANUFACTURER") "Taiyo Yuden")
        (field (name "MANUFACTURER PART NUMBER") "LMK325BJ107MM-T")
        (field (name "VOLTAGE - RATED") "10V")
        (field (name "PACKAGE") "1210")
      )
      (libsource (lib "ALCT_MEZ_SPARTAN6_Library") (part "LMK325BJ107MM-T"))
    )
    (comp (ref "C471")
      (value "100uF")
      (footprint "MC_S6/SM/C_1210_IPC")
      (description "CAP CER 100UF 10V X5R 1210")
      (fields
        (field (name "MANUFACTURER") "Taiyo Yuden")
        (field (name "MANUFACTURER PART NUMBER") "LMK325BJ107MM-T")
        (field (name "VOLTAGE - RATED") "10V")
        (field (name "PACKAGE") "1210")
      )
      (libsource (lib "ALCT_MEZ_SPARTAN6_Library") (part "LMK325BJ107MM-T"))
    )
    (comp (ref "C472")
      (value "100uF")
      (footprint "MC_S6/SM/C_1210_IPC")
      (description "CAP CER 100UF 10V X5R 1210")
      (fields
        (field (name "MANUFACTURER") "Taiyo Yuden")
        (field (name "MANUFACTURER PART NUMBER") "LMK325BJ107MM-T")
        (field (name "VOLTAGE - RATED") "10V")
        (field (name "PACKAGE") "1210")
      )
      (libsource (lib "ALCT_MEZ_SPARTAN6_Library") (part "LMK325BJ107MM-T"))
    )
    (comp (ref "U1")
      (value "XC6SLX150T-3FGG900C")
      (footprint "MC_S6/BGA/FGG900")
      (fields (field (name "MANUFACTURER") "Xilinx Inc."))
      (libsource (lib "ALCT_MEZ_SPARTAN6_Library") (part "XC6SLX150T-3FGG900C"))
    )
  )
  (nets
    (net (code "1") (name "+1V2") (class "Default")
      (node (ref "C271") (pin "1") (pinfunction "1_1") (pintype "passive"))
      (node (ref "C272") (pin "1") (pinfunction "1_1") (pintype "passive"))
      (node (ref "C273") (pin "1") (pinfunction "1_1") (pintype "passive"))
      (node (ref "C274") (pin "1") (pinfunction "1_1") (pintype "passive"))
      (node (ref "C275") (pin "1") (pinfunction "1_1") (pintype "passive"))
      (node (ref "C276") (pin "1") (pinfunction "1_1") (pintype "passive"))
      (node (ref "C371") (pin "1") (pinfunction "1_1") (pintype "passive"))
      (node (ref "C372") (pin "1") (pinfunction "1_1") (pintype "passive"))
      (node (ref "C373") (pin "1") (pinfunction "1_1") (pintype "passive"))
      (node (ref "C374") (pin "1") (pinfunction "1_1") (pintype "passive"))
      (node (ref "C375") (pin "1") (pinfunction "1_1") (pintype "passive"))
      (node (ref "C471") (pin "1") (pinfunction "1_1") (pintype "passive"))
      (node (ref "C472") (pin "1") (pinfunction "1_1") (pintype "passive"))
      (node (ref "U1") (pin "N11") (pinfunction "VCCINT_N11") (pintype "power_in"))
      (node (ref "U1") (pin "N12") (pinfunction "VCCINT_N12") (pintype "power_in"))
      (node (ref "U1") (pin "N15") (pinfunction "VCCINT_N15") (pintype "power_in"))
      (node (ref "U1") (pin "N16") (pinfunction "VCCINT_N16") (pintype "power_in"))
      (node (ref "U1") (pin "N19") (pinfunction "VCCINT_N19") (pintype "power_in"))
      (node (ref "U1") (pin "N20") (pinfunction "VCCINT_N20") (pintype "power_in"))
      (node (ref "U1") (pin "P11") (pinfunction "VCCINT_P11") (pintype "power_in"))
      (node (ref "U1") (pin "P12") (pinfunction "VCCINT_P12") (pintype "power_in"))
      (node (ref "U1") (pin "P15") (pinfunction "VCCINT_P15") (pintype "power_in"))
      (node (ref "U1") (pin "P16") (pinfunction "VCCINT_P16") (pintype "power_in"))
      (node (ref "U1") (pin "P19") (pinfunction "VCCINT_P19") (pintype "power_in"))
      (node (ref "U1") (pin "R13") (pinfunction "VCCINT_R13") (pintype "power_in"))
      (node (ref "U1") (pin "R14") (pinfunction "VCCINT_R14") (pintype "power_in"))
      (node (ref "U1") (pin "R17") (pinfunction "VCCINT_R17") (pintype "power_in"))
      (node (ref "U1") (pin "R18") (pinfunction "VCCINT_R18") (pintype "power_in"))
      (node (ref "U1") (pin "T13") (pinfunction "VCCINT_T13") (pintype "power_in"))
      (node (ref "U1") (pin "T14") (pinfunction "VCCINT_T14") (pintype "power_in"))
      (node (ref "U1") (pin "T17") (pinfunction "VCCINT_T17") (pintype "power_in"))
      (node (ref "U1") (pin "T18") (pinfunction "VCCINT_T18") (pintype "power_in"))
      (node (ref "U1") (pin "U12") (pinfunction "VCCINT_U12") (pintype "power_in"))
      (node (ref "U1") (pin "U15") (pinfunction "VCCINT_U15") (pintype "power_in"))
      (node (ref "U1") (pin "U16") (pinfunction "VCCINT_U16") (pintype "power_in"))
      (node (ref "U1") (pin "U19") (pinfunction "VCCINT_U19") (pintype "power_in"))
      (node (ref "U1") (pin "U20") (pinfunction "VCCINT_U20") (pintype "power_in"))
      (node (ref "U1") (pin "V11") (pinfunction "VCCINT_V11") (pintype "power_in"))
      (node (ref "U1") (pin "V12") (pinfunction "VCCINT_V12") (pintype "power_in"))
      (node (ref "U1") (pin "V15") (pinfunction "VCCINT_V15") (pintype "power_in"))
      (node (ref "U1") (pin "V16") (pinfunction "VCCINT_V16") (pintype "power_in"))
      (node (ref "U1") (pin "V19") (pinfunction "VCCINT_V19") (pintype "power_in"))
      (node (ref "U1") (pin "V20") (pinfunction "VCCINT_V20") (pintype "power_in"))
    )
    (net (code "2") (name "+2V5_AUX") (class "Default")
      (node (ref "C261") (pin "1") (pinfunction "1_1") (pintype "passive"))
      (node (ref "C262") (pin "1") (pinfunction "1_1") (pintype "passive"))
      (node (ref "C263") (pin "1") (pinfunction "1_1") (pintype "passive"))
      (node (ref "C264") (pin "1") (pinfunction "1_1") (pintype "passive"))
      (node (ref "C265") (pin "1") (pinfunction "1_1") (pintype "passive"))
      (node (ref "C266") (pin "1") (pinfunction "1_1") (pintype "passive"))
      (node (ref "C267") (pin "1") (pinfunction "1_1") (pintype "passive"))
      (node (ref "C268") (pin "1") (pinfunction "1_1") (pintype "passive"))
      (node (ref "C361") (pin "1") (pinfunction "1_1") (pintype "passive"))
      (node (ref "C362") (pin "1") (pinfunction "1_1") (pintype "passive"))
      (node (ref "C363") (pin "1") (pinfunction "1_1") (pintype "passive"))
      (node (ref "C364") (pin "1") (pinfunction "1_1") (pintype "passive"))
      (node (ref "C365") (pin "1") (pinfunction "1_1") (pintype "passive"))
      (node (ref "C461") (pin "1") (pinfunction "1_1") (pintype "passive"))
      (node (ref "C462") (pin "1") (pinfunction "1_1") (pintype "passive"))
      (node (ref "U1") (pin "AB24") (pinfunction "VCCAUX_AB24") (pintype "power_in"))
      (node (ref "U1") (pin "AC7") (pinfunction "VCCAUX_AC7") (pintype "power_in"))
      (node (ref "U1") (pin "AG23") (pinfunction "VCCAUX_AG23") (pintype "power_in"))
      (node (ref "U1") (pin "AG9") (pinfunction "VCCAUX_AG9") (pintype "power_in"))
      (node (ref "U1") (pin "D23") (pinfunction "VCCAUX_D23") (pintype "power_in"))
      (node (ref "U1") (pin "D9") (pinfunction "VCCAUX_D9") (pintype "power_in"))
      (node (ref "U1") (pin "G6") (pinfunction "VCCAUX_G6") (pintype "power_in"))
      (node (ref "U1") (pin "H24") (pinfunction "VCCAUX_H24") (pintype "power_in"))
      (node (ref "U1") (pin "J15") (pinfunction "VCCAUX_J15") (pintype "power_in"))
      (node (ref "U1") (pin "J23") (pinfunction "VCCAUX_J23") (pintype "power_in"))
      (node (ref "U1") (pin "J7") (pinfunction "VCCAUX_J7") (pintype "power_in"))
      (node (ref "U1") (pin "J9") (pinfunction "VCCAUX_J9") (pintype "power_in"))
      (node (ref "U1") (pin "L22") (pinfunction "VCCAUX_L22") (pintype "power_in"))
      (node (ref "U1") (pin "M11") (pinfunction "VCCAUX_M11") (pintype "power_in"))
      (node (ref "U1") (pin "M14") (pinfunction "VCCAUX_M14") (pintype "power_in"))
      (node (ref "U1") (pin "M25") (pinfunction "VCCAUX_M25") (pintype "power_in"))
      (node (ref "U1") (pin "N6") (pinfunction "VCCAUX_N6") (pintype "power_in"))
      (node (ref "U1") (pin "R10") (pinfunction "VCCAUX_R10") (pintype "power_in"))
      (node (ref "U1") (pin "T21") (pinfunction "VCCAUX_T21") (pintype "power_in"))
      (node (ref "U1") (pin "U10") (pinfunction "VCCAUX_U10") (pintype "power_in"))
      (node (ref "U1") (pin "V21") (pinfunction "VCCAUX_V21") (pintype "power_in"))
      (node (ref "U1") (pin "V25") (pinfunction "VCCAUX_V25") (pintype "power_in"))
      (node (ref "U1") (pin "V6") (pinfunction "VCCAUX_V6") (pintype "power_in"))
      (node (ref "U1") (pin "W13") (pinfunction "VCCAUX_W13") (pintype "power_in"))
      (node (ref "U1") (pin "W15") (pinfunction "VCCAUX_W15") (pintype "power_in"))
      (node (ref "U1") (pin "W17") (pinfunction "VCCAUX_W17") (pintype "power_in"))
      (node (ref "U1") (pin "Y18") (pinfunction "VCCAUX_Y18") (pintype "power_in"))
    )
    (net (code "3") (name "+3V3") (class "Default")
      (node (ref "C201") (pin "1") (pinfunction "1_1") (pintype "passive"))
      (node (ref "C202") (pin "1") (pinfunction "1_1") (pintype "passive"))
      (node (ref "C203") (pin "1") (pinfunction "1_1") (pintype "passive"))
      (node (ref "C204") (pin "1") (pinfunction "1_1") (pintype "passive"))
      (node (ref "C205") (pin "1") (pinfunction "1_1") (pintype "passive"))
      (node (ref "C211") (pin "1") (pinfunction "1_1") (pintype "passive"))
      (node (ref "C212") (pin "1") (pinfunction "1_1") (pintype "passive"))
      (node (ref "C213") (pin "1") (pinfunction "1_1") (pintype "passive"))
      (node (ref "C214") (pin "1") (pinfunction "1_1") (pintype "passive"))
      (node (ref "C215") (pin "1") (pinfunction "1_1") (pintype "passive"))
      (node (ref "C221") (pin "1") (pinfunction "1_1") (pintype "passive"))
      (node (ref "C222") (pin "1") (pinfunction "1_1") (pintype "passive"))
      (node (ref "C223") (pin "1") (pinfunction "1_1") (pintype "passive"))
      (node (ref "C224") (pin "1") (pinfunction "1_1") (pintype "passive"))
      (node (ref "C225") (pin "1") (pinfunction "1_1") (pintype "passive"))
      (node (ref "C231") (pin "1") (pinfunction "1_1") (pintype "passive"))
      (node (ref "C232") (pin "1") (pinfunction "1_1") (pintype "passive"))
      (node (ref "C233") (pin "1") (pinfunction "1_1") (pintype "passive"))
      (node (ref "C234") (pin "1") (pinfunction "1_1") (pintype "passive"))
      (node (ref "C235") (pin "1") (pinfunction "1_1") (pintype "passive"))
      (node (ref "C241") (pin "1") (pinfunction "1_1") (pintype "passive"))
      (node (ref "C242") (pin "1") (pinfunction "1_1") (pintype "passive"))
      (node (ref "C243") (pin "1") (pinfunction "1_1") (pintype "passive"))
      (node (ref "C244") (pin "1") (pinfunction "1_1") (pintype "passive"))
      (node (ref "C251") (pin "1") (pinfunction "1_1") (pintype "passive"))
      (node (ref "C252") (pin "1") (pinfunction "1_1") (pintype "passive"))
      (node (ref "C253") (pin "1") (pinfunction "1_1") (pintype "passive"))
      (node (ref "C254") (pin "1") (pinfunction "1_1") (pintype "passive"))
      (node (ref "C301") (pin "1") (pinfunction "1_1") (pintype "passive"))
      (node (ref "C302") (pin "1") (pinfunction "1_1") (pintype "passive"))
      (node (ref "C311") (pin "1") (pinfunction "1_1") (pintype "passive"))
      (node (ref "C312") (pin "1") (pinfunction "1_1") (pintype "passive"))
      (node (ref "C321") (pin "1") (pinfunction "1_1") (pintype "passive"))
      (node (ref "C322") (pin "1") (pinfunction "1_1") (pintype "passive"))
      (node (ref "C331") (pin "1") (pinfunction "1_1") (pintype "passive"))
      (node (ref "C332") (pin "1") (pinfunction "1_1") (pintype "passive"))
      (node (ref "C341") (pin "1") (pinfunction "1_1") (pintype "passive"))
      (node (ref "C342") (pin "1") (pinfunction "1_1") (pintype "passive"))
      (node (ref "C351") (pin "1") (pinfunction "1_1") (pintype "passive"))
      (node (ref "C401") (pin "1") (pinfunction "1_1") (pintype "passive"))
      (node (ref "C411") (pin "1") (pinfunction "1_1") (pintype "passive"))
      (node (ref "C421") (pin "1") (pinfunction "1_1") (pintype "passive"))
      (node (ref "C431") (pin "1") (pinfunction "1_1") (pintype "passive"))
      (node (ref "C441") (pin "1") (pinfunction "1_1") (pintype "passive"))
      (node (ref "C451") (pin "1") (pinfunction "1_1") (pintype "passive"))
      (node (ref "U1") (pin "AA12") (pinfunction "VCCO_2_AA12") (pintype "power_in"))
      (node (ref "U1") (pin "AA16") (pinfunction "VCCO_2_AA16") (pintype "power_in"))
      (node (ref "U1") (pin "AA20") (pinfunction "VCCO_2_AA20") (pintype "power_in"))
      (node (ref "U1") (pin "AA23") (pinfunction "VCCO_1_AA23") (pintype "power_in"))
      (node (ref "U1") (pin "AA8") (pinfunction "VCCO_3_AA8") (pintype "power_in"))
      (node (ref "U1") (pin "AC10") (pinfunction "VCCO_2_AC10") (pintype "power_in"))
      (node (ref "U1") (pin "AC18") (pinfunction "VCCO_2_AC18") (pintype "power_in"))
      (node (ref "U1") (pin "AC2") (pinfunction "VCCO_3_AC2") (pintype "power_in"))
      (node (ref "U1") (pin "AC26") (pinfunction "VCCO_1_AC26") (pintype "power_in"))
      (node (ref "U1") (pin "AD13") (pinfunction "VCCO_2_AD13") (pintype "power_in"))
      (node (ref "U1") (pin "AD21") (pinfunction "VCCO_2_AD21") (pintype "power_in"))
      (node (ref "U1") (pin "AD23") (pinfunction "VCCO_2_AD23") (pintype "power_in"))
      (node (ref "U1") (pin "AD29") (pinfunction "VCCO_1_AD29") (pintype "power_in"))
      (node (ref "U1") (pin "AD5") (pinfunction "VCCO_3_AD5") (pintype "power_in"))
      (node (ref "U1") (pin "AE16") (pinfunction "VCCO_2_AE16") (pintype "power_in"))
      (node (ref "U1") (pin "AF8") (pinfunction "VCCO_2_AF8") (pintype "power_in"))
      (node (ref "U1") (pin "AG2") (pinfunction "VCCO_3_AG2") (pintype "power_in"))
      (node (ref "U1") (pin "AH25") (pinfunction "VCCO_2_AH25") (pintype "power_in"))
      (node (ref "U1") (pin "AH29") (pinfunction "VCCO_1_AH29") (pintype "power_in"))
      (node (ref "U1") (pin "AJ16") (pinfunction "VCCO_2_AJ16") (pintype "power_in"))
      (node (ref "U1") (pin "AJ27") (pinfunction "VCCO_1_AJ27") (pintype "power_in"))
      (node (ref "U1") (pin "AJ3") (pinfunction "VCCO_3_AJ3") (pintype "power_in"))
      (node (ref "U1") (pin "AJ7") (pinfunction "VCCO_2_AJ7") (pintype "power_in"))
      (node (ref "U1") (pin "B16") (pinfunction "VCCO_0_B16") (pintype "power_in"))
      (node (ref "U1") (pin "B28") (pinfunction "VCCO_5_B28") (pintype "power_in"))
      (node (ref "U1") (pin "B4") (pinfunction "VCCO_4_B4") (pintype "power_in"))
      (node (ref "U1") (pin "C2") (pinfunction "VCCO_4_C2") (pintype "power_in"))
      (node (ref "U1") (pin "C25") (pinfunction "VCCO_0_C25") (pintype "power_in"))
      (node (ref "U1") (pin "C7") (pinfunction "VCCO_0_C7") (pintype "power_in"))
      (node (ref "U1") (pin "D29") (pinfunction "VCCO_5_D29") (pintype "power_in"))
      (node (ref "U1") (pin "F16") (pinfunction "VCCO_0_F16") (pintype "power_in"))
      (node (ref "U1") (pin "G13") (pinfunction "VCCO_0_G13") (pintype "power_in"))
      (node (ref "U1") (pin "G2") (pinfunction "VCCO_4_G2") (pintype "power_in"))
      (node (ref "U1") (pin "G23") (pinfunction "VCCO_0_G23") (pintype "power_in"))
      (node (ref "U1") (pin "G26") (pinfunction "VCCO_5_G26") (pintype "power_in"))
      (node (ref "U1") (pin "G8") (pinfunction "VCCO_0_G8") (pintype "power_in"))
      (node (ref "U1") (pin "H10") (pinfunction "VCCO_0_H10") (pintype "power_in"))
      (node (ref "U1") (pin "H20") (pinfunction "VCCO_0_H20") (pintype "power_in"))
      (node (ref "U1") (pin "H29") (pinfunction "VCCO_5_H29") (pintype "power_in"))
      (node (ref "U1") (pin "H5") (pinfunction "VCCO_4_H5") (pintype "power_in"))
      (node (ref "U1") (pin "J17") (pinfunction "VCCO_0_J17") (pintype "power_in"))
      (node (ref "U1") (pin "J25") (pinfunction "VCCO_5_J25") (pintype "power_in"))
      (node (ref "U1") (pin "K13") (pinfunction "VCCO_0_K13") (pintype "power_in"))
      (node (ref "U1") (pin "K24") (pinfunction "VCCO_5_K24") (pintype "power_in"))
      (node (ref "U1") (pin "K6") (pinfunction "VCCO_4_K6") (pintype "power_in"))
      (node (ref "U1") (pin "L15") (pinfunction "VCCO_0_L15") (pintype "power_in"))
      (node (ref "U1") (pin "L2") (pinfunction "VCCO_4_L2") (pintype "power_in"))
      (node (ref "U1") (pin "L26") (pinfunction "VCCO_5_L26") (pintype "power_in"))
      (node (ref "U1") (pin "L9") (pinfunction "VCCO_0_L9") (pintype "power_in"))
      (node (ref "U1") (pin "M17") (pinfunction "VCCO_0_M17") (pintype "power_in"))
      (node (ref "U1") (pin "M21") (pinfunction "VCCO_0_M21") (pintype "power_in"))
      (node (ref "U1") (pin "M29") (pinfunction "VCCO_5_M29") (pintype "power_in"))
      (node (ref "U1") (pin "M5") (pinfunction "VCCO_4_M5") (pintype "power_in"))
      (node (ref "U1") (pin "M8") (pinfunction "VCCO_3_M8") (pintype "power_in"))
      (node (ref "U1") (pin "N23") (pinfunction "VCCO_1_N23") (pintype "power_in"))
      (node (ref "U1") (pin "P21") (pinfunction "VCCO_1_P21") (pintype "power_in"))
      (node (ref "U1") (pin "P9") (pinfunction "VCCO_3_P9") (pintype "power_in"))
      (node (ref "U1") (pin "R2") (pinfunction "VCCO_3_R2") (pintype "power_in"))
      (node (ref "U1") (pin "R23") (pinfunction "VCCO_1_R23") (pintype "power_in"))
      (node (ref "U1") (pin "R26") (pinfunction "VCCO_1_R26") (pintype "power_in"))
      (node (ref "U1") (pin "R8") (pinfunction "VCCO_3_R8") (pintype "power_in"))
      (node (ref "U1") (pin "T29") (pinfunction "VCCO_1_T29") (pintype "power_in"))
      (node (ref "U1") (pin "T5") (pinfunction "VCCO_3_T5") (pintype "power_in"))
      (node (ref "U1") (pin "U23") (pinfunction "VCCO_1_U23") (pintype "power_in"))
      (node (ref "U1") (pin "U8") (pinfunction "VCCO_3_U8") (pintype "power_in"))
      (node (ref "U1") (pin "W2") (pinfunction "VCCO_3_W2") (pintype "power_in"))
      (node (ref "U1") (pin "W23") (pinfunction "VCCO_1_W23") (pintype "power_in"))
      (node (ref "U1") (pin "W26") (pinfunction "VCCO_1_W26") (pintype "power_in"))
      (node (ref "U1") (pin "Y10") (pinfunction "VCCO_3_Y10") (pintype "power_in"))
      (node (ref "U1") (pin "Y29") (pinfunction "VCCO_1_Y29") (pintype "power_in"))
      (node (ref "U1") (pin "Y5") (pinfunction "VCCO_3_Y5") (pintype "power_in"))
    )
    (net (code "4") (name "GND") (class "Default")
      (node (ref "C201") (pin "2") (pinfunction "2_2") (pintype "passive"))
      (node (ref "C202") (pin "2") (pinfunction "2_2") (pintype "passive"))
      (node (ref "C203") (pin "2") (pinfunction "2_2") (pintype "passive"))
      (node (ref "C204") (pin "2") (pinfunction "2_2") (pintype "passive"))
      (node (ref "C205") (pin "2") (pinfunction "2_2") (pintype "passive"))
      (node (ref "C211") (pin "2") (pinfunction "2_2") (pintype "passive"))
      (node (ref "C212") (pin "2") (pinfunction "2_2") (pintype "passive"))
      (node (ref "C213") (pin "2") (pinfunction "2_2") (pintype "passive"))
      (node (ref "C214") (pin "2") (pinfunction "2_2") (pintype "passive"))
      (node (ref "C215") (pin "2") (pinfunction "2_2") (pintype "passive"))
      (node (ref "C221") (pin "2") (pinfunction "2_2") (pintype "passive"))
      (node (ref "C222") (pin "2") (pinfunction "2_2") (pintype "passive"))
      (node (ref "C223") (pin "2") (pinfunction "2_2") (pintype "passive"))
      (node (ref "C224") (pin "2") (pinfunction "2_2") (pintype "passive"))
      (node (ref "C225") (pin "2") (pinfunction "2_2") (pintype "passive"))
      (node (ref "C231") (pin "2") (pinfunction "2_2") (pintype "passive"))
      (node (ref "C232") (pin "2") (pinfunction "2_2") (pintype "passive"))
      (node (ref "C233") (pin "2") (pinfunction "2_2") (pintype "passive"))
      (node (ref "C234") (pin "2") (pinfunction "2_2") (pintype "passive"))
      (node (ref "C235") (pin "2") (pinfunction "2_2") (pintype "passive"))
      (node (ref "C241") (pin "2") (pinfunction "2_2") (pintype "passive"))
      (node (ref "C242") (pin "2") (pinfunction "2_2") (pintype "passive"))
      (node (ref "C243") (pin "2") (pinfunction "2_2") (pintype "passive"))
      (node (ref "C244") (pin "2") (pinfunction "2_2") (pintype "passive"))
      (node (ref "C251") (pin "2") (pinfunction "2_2") (pintype "passive"))
      (node (ref "C252") (pin "2") (pinfunction "2_2") (pintype "passive"))
      (node (ref "C253") (pin "2") (pinfunction "2_2") (pintype "passive"))
      (node (ref "C254") (pin "2") (pinfunction "2_2") (pintype "passive"))
      (node (ref "C261") (pin "2") (pinfunction "2_2") (pintype "passive"))
      (node (ref "C262") (pin "2") (pinfunction "2_2") (pintype "passive"))
      (node (ref "C263") (pin "2") (pinfunction "2_2") (pintype "passive"))
      (node (ref "C264") (pin "2") (pinfunction "2_2") (pintype "passive"))
      (node (ref "C265") (pin "2") (pinfunction "2_2") (pintype "passive"))
      (node (ref "C266") (pin "2") (pinfunction "2_2") (pintype "passive"))
      (node (ref "C267") (pin "2") (pinfunction "2_2") (pintype "passive"))
      (node (ref "C268") (pin "2") (pinfunction "2_2") (pintype "passive"))
      (node (ref "C271") (pin "2") (pinfunction "2_2") (pintype "passive"))
      (node (ref "C272") (pin "2") (pinfunction "2_2") (pintype "passive"))
      (node (ref "C273") (pin "2") (pinfunction "2_2") (pintype "passive"))
      (node (ref "C274") (pin "2") (pinfunction "2_2") (pintype "passive"))
      (node (ref "C275") (pin "2") (pinfunction "2_2") (pintype "passive"))
      (node (ref "C276") (pin "2") (pinfunction "2_2") (pintype "passive"))
      (node (ref "C301") (pin "2") (pinfunction "2_2") (pintype "passive"))
      (node (ref "C302") (pin "2") (pinfunction "2_2") (pintype "passive"))
      (node (ref "C311") (pin "2") (pinfunction "2_2") (pintype "passive"))
      (node (ref "C312") (pin "2") (pinfunction "2_2") (pintype "passive"))
      (node (ref "C321") (pin "2") (pinfunction "2_2") (pintype "passive"))
      (node (ref "C322") (pin "2") (pinfunction "2_2") (pintype "passive"))
      (node (ref "C331") (pin "2") (pinfunction "2_2") (pintype "passive"))
      (node (ref "C332") (pin "2") (pinfunction "2_2") (pintype "passive"))
      (node (ref "C341") (pin "2") (pinfunction "2_2") (pintype "passive"))
      (node (ref "C342") (pin "2") (pinfunction "2_2") (pintype "passive"))
      (node (ref "C351") (pin "2") (pinfunction "2_2") (pintype "passive"))
      (node (ref "C361") (pin "2") (pinfunction "2_2") (pintype "passive"))
      (node (ref "C362") (pin "2") (pinfunction "2_2") (pintype "passive"))
      (node (ref "C363") (pin "2") (pinfunction "2_2") (pintype "passive"))
      (node (ref "C364") (pin "2") (pinfunction "2_2") (pintype "passive"))
      (node (ref "C365") (pin "2") (pinfunction "2_2") (pintype "passive"))
      (node (ref "C371") (pin "2") (pinfunction "2_2") (pintype "passive"))
      (node (ref "C372") (pin "2") (pinfunction "2_2") (pintype "passive"))
      (node (ref "C373") (pin "2") (pinfunction "2_2") (pintype "passive"))
      (node (ref "C374") (pin "2") (pinfunction "2_2") (pintype "passive"))
      (node (ref "C375") (pin "2") (pinfunction "2_2") (pintype "passive"))
      (node (ref "C401") (pin "2") (pinfunction "2_2") (pintype "passive"))
      (node (ref "C411") (pin "2") (pinfunction "2_2") (pintype "passive"))
      (node (ref "C421") (pin "2") (pinfunction "2_2") (pintype "passive"))
      (node (ref "C431") (pin "2") (pinfunction "2_2") (pintype "passive"))
      (node (ref "C441") (pin "2") (pinfunction "2_2") (pintype "passive"))
      (node (ref "C451") (pin "2") (pinfunction "2_2") (pintype "passive"))
      (node (ref "C461") (pin "2") (pinfunction "2_2") (pintype "passive"))
      (node (ref "C462") (pin "2") (pinfunction "2_2") (pintype "passive"))
      (node (ref "C471") (pin "2") (pinfunction "2_2") (pintype "passive"))
      (node (ref "C472") (pin "2") (pinfunction "2_2") (pintype "passive"))
    )
    (net (code "5") (name "unconnected-(U1I-VCCINT-PadU11)") (class "Default")
      (node (ref "U1") (pin "U11") (pinfunction "VCCINT_U11") (pintype "power_in"))
    )
  )
)
